# ProPrj___2025-12-14-16-26-23.net
KiCad netlist of a schematic drawn in EasyEDA Pro
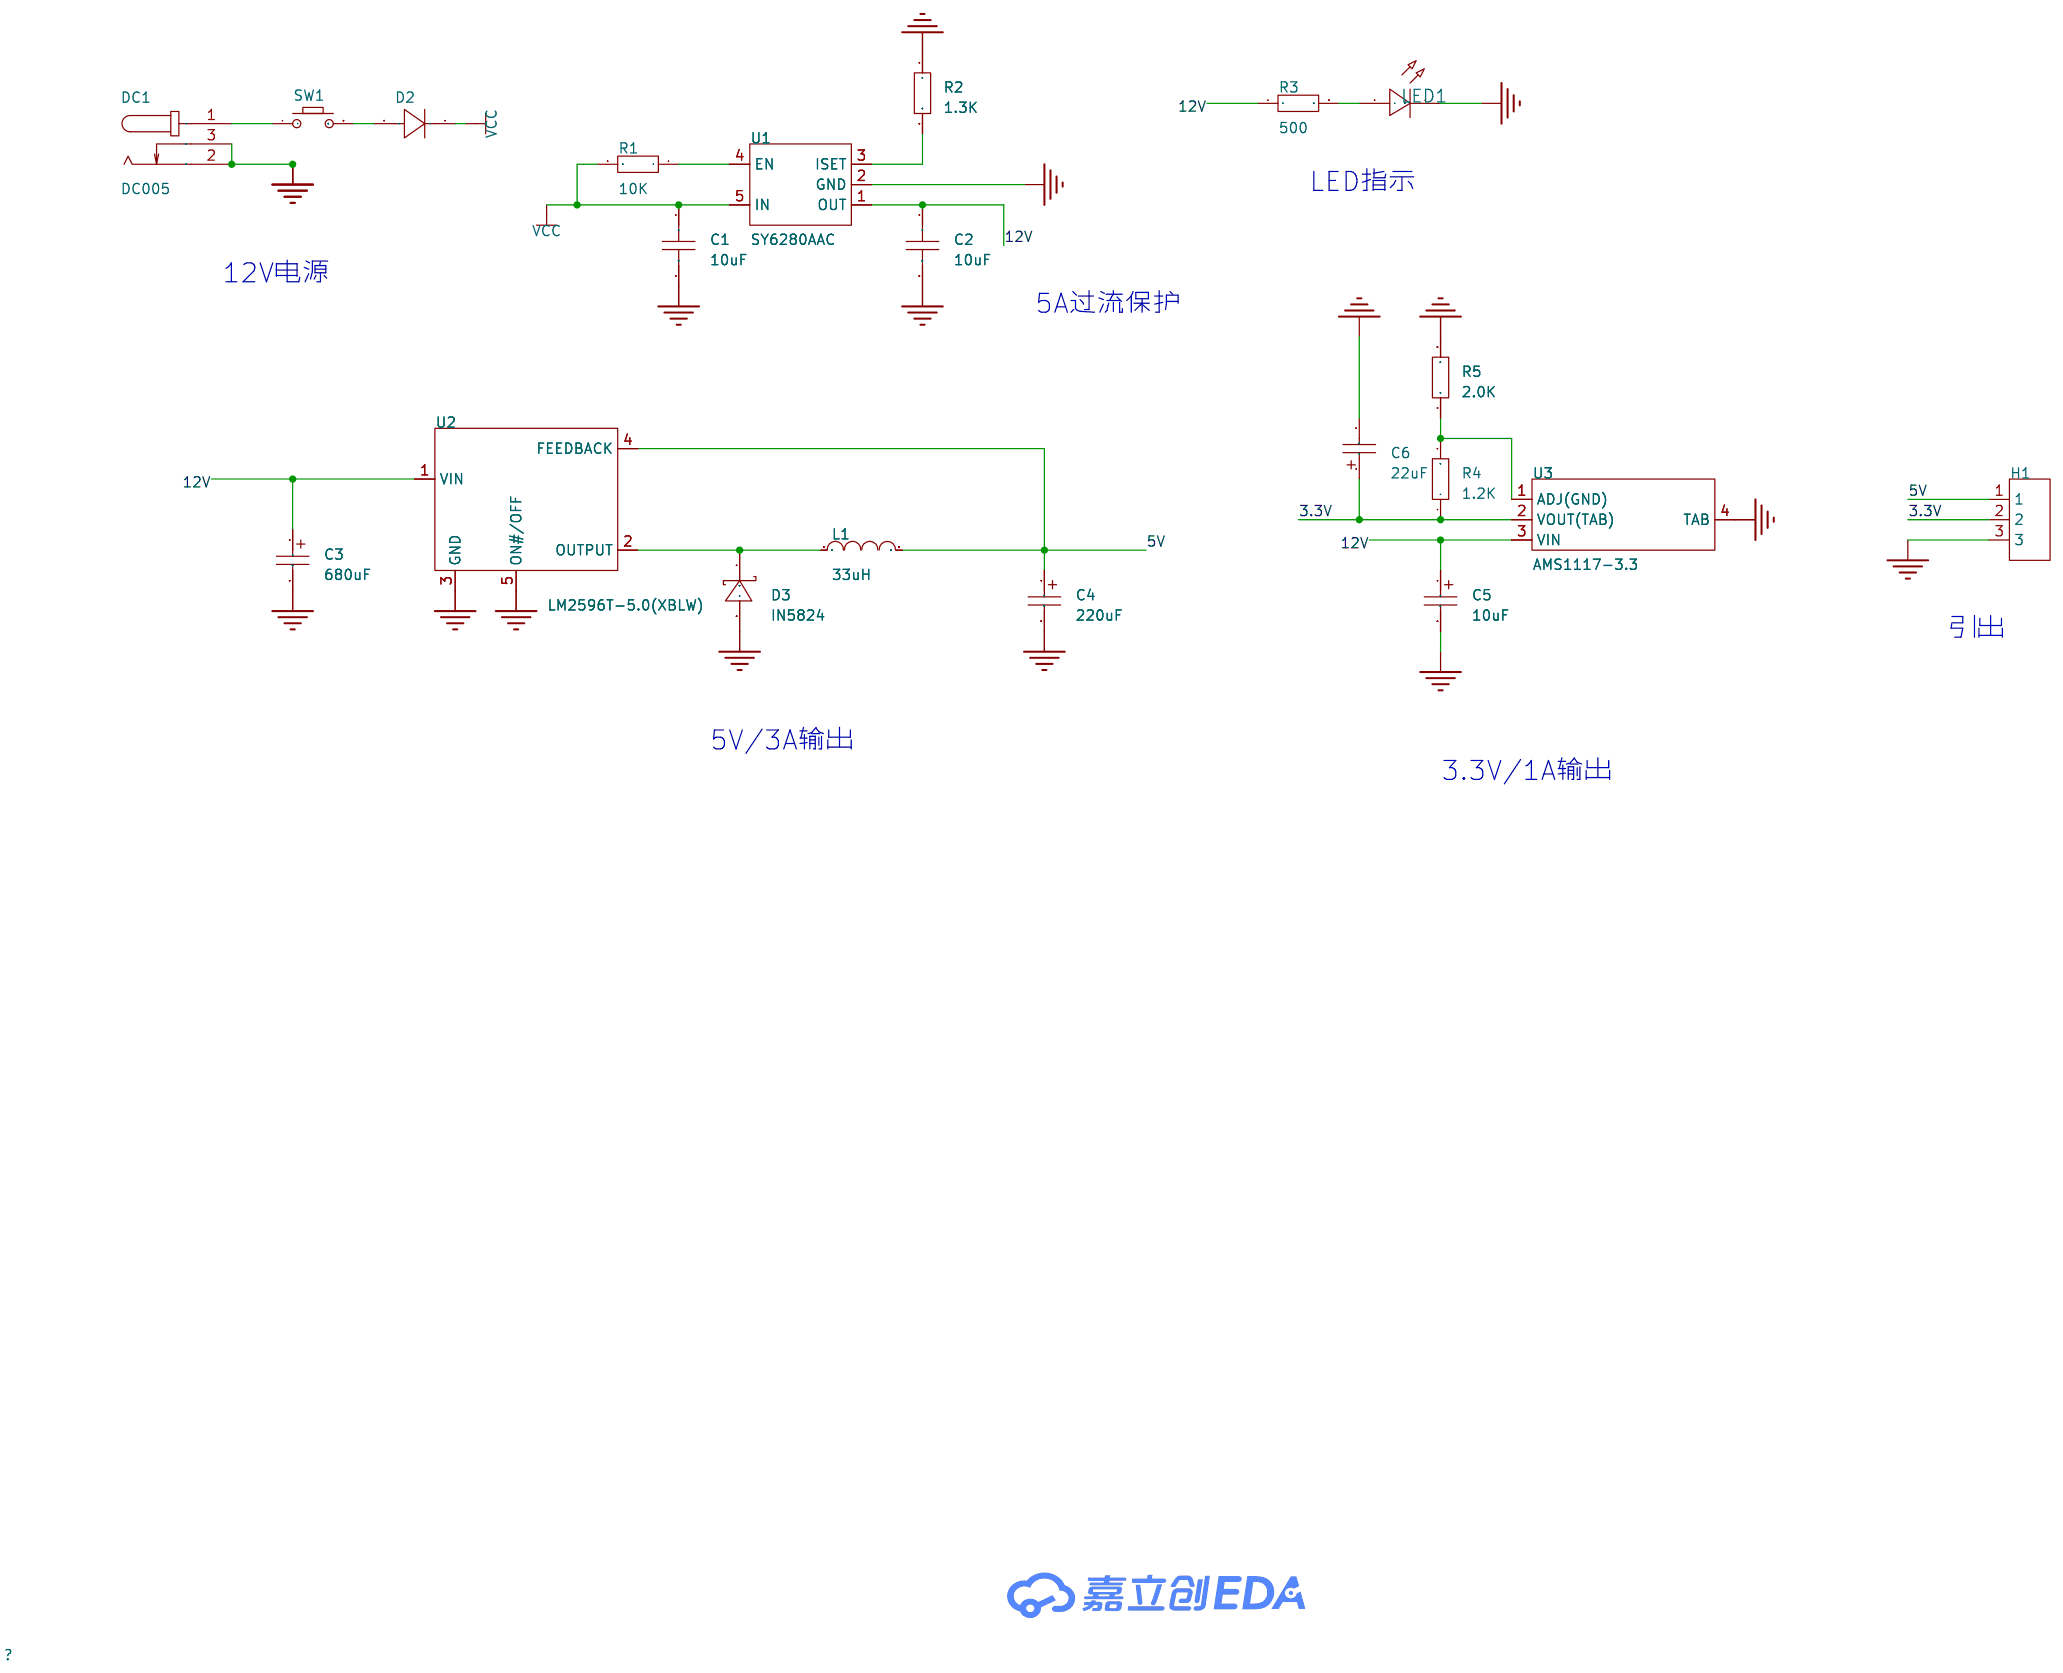
[diagram p0: schematic sheet]

(export (version "E")
  (design (tool "Eeschema 10.0.6"))
  (components
    (comp (ref "C1")
      (value "10uF")
      (footprint "easyedapro:C0603")
      (libsource (lib "easyedapro") (part "Capacitance"))
    )
    (comp (ref "C2")
      (value "10uF")
      (footprint "easyedapro:C0603")
      (libsource (lib "easyedapro") (part "Capacitance"))
    )
    (comp (ref "C3")
      (value "680uF")
      (footprint "easyedapro:C_Ele_SMD_3x5.4mm")
      (libsource (lib "easyedapro") (part "CAP"))
    )
    (comp (ref "C4")
      (value "220uF")
      (footprint "easyedapro:C_Ele_SMD_3x5.4mm")
      (libsource (lib "easyedapro") (part "CAP"))
    )
    (comp (ref "C5")
      (value "10uF")
      (footprint "easyedapro:C_Ele_SMD_3x5.4mm")
      (libsource (lib "easyedapro") (part "CAP"))
    )
    (comp (ref "C6")
      (value "22uF")
      (footprint "easyedapro:C_Ele_SMD_3x5.4mm")
      (libsource (lib "easyedapro") (part "CAP"))
    )
    (comp (ref "D2")
      (value "~")
      (footprint "easyedapro:DO_1N4007")
      (libsource (lib "easyedapro") (part "D_1N4007"))
    )
    (comp (ref "D3")
      (value "IN5824")
      (footprint "easyedapro:SMAF_L3.5-W2.6-LS4.7-RD")
      (libsource (lib "easyedapro") (part "IN5824"))
    )
    (comp (ref "DC1")
      (value "DC005")
      (footprint "easyedapro:DC-IN-TH_DC005")
      (description "连接器类型:DC电源插座;安装方式:弯插;触点内径:2mm;触点外径:6.3mm;额定电流:500mA;额定电压:12V;工作温度:-30°C~+70°C;")
      (fields (field (name "Manufacturer") "SHOU HAN(首韩)"))
      (libsource (lib "easyedapro") (part "DC005_C431533"))
    )
    (comp (ref "H1")
      (value "~")
      (footprint "easyedapro:HDR-TH_3P-P2.54-V-F")
      (libsource (lib "easyedapro") (part "PM254V-11-03-H85"))
    )
    (comp (ref "L1")
      (value "33uH")
      (footprint "easyedapro:L0603")
      (libsource (lib "easyedapro") (part "SDFL1608S100KTF"))
    )
    (comp (ref "LED1")
      (value "~")
      (footprint "easyedapro:LED_0603")
      (libsource (lib "easyedapro") (part "LED_R"))
    )
    (comp (ref "R1") (value "10K") (footprint "easyedapro:R0603") (libsource (lib "easyedapro") (part "电阻")))
    (comp (ref "R2") (value "1.3K") (footprint "easyedapro:R0603") (libsource (lib "easyedapro") (part "电阻")))
    (comp (ref "R3") (value "500") (footprint "easyedapro:R0603") (libsource (lib "easyedapro") (part "电阻")))
    (comp (ref "R4") (value "1.2K") (footprint "easyedapro:R0603") (libsource (lib "easyedapro") (part "电阻")))
    (comp (ref "R5") (value "2.0K") (footprint "easyedapro:R0603") (libsource (lib "easyedapro") (part "电阻")))
    (comp (ref "SW1")
      (value "~")
      (footprint "easyedapro:Key_TH_3.5x6x4.3")
      (libsource (lib "easyedapro") (part "Key_TH_3.5x6x4.3"))
    )
    (comp (ref "U1")
      (value "SY6280AAC")
      (footprint "easyedapro:SOT-23-5_L3.0-W1.7-P0.95-LS2.8-BR")
      (libsource (lib "easyedapro") (part "SY6280AAC_C9900003867"))
    )
    (comp (ref "U2")
      (value "LM2596T-5.0(XBLW)")
      (footprint "easyedapro:TO-220-5L_L10.2-W4.5-P1.71-L")
      (description "功能类型:降压型;工作电压:6V~40V;输出电压:5V;输出电流:3A;输出类型:固定;")
      (fields (field (name "Manufacturer") "XBLW(芯伯乐)"))
      (libsource (lib "easyedapro") (part "LM2596T-5.0(XBLW)"))
    )
    (comp (ref "U3")
      (value "AMS1117-3.3")
      (footprint "easyedapro:SOT-223-4_L6.5-W3.5-P2.30-LS7.0-BR")
      (description "输出类型:固定;工作电压:12V;输出电压:3.3V;输出电流:1A;电源纹波抑制比(PSRR):60dB@(120Hz);输出极性:正极;")
      (fields (field (name "Manufacturer") "UMW(友台半导体)"))
      (libsource (lib "easyedapro") (part "AMS1117-3.3_C347222"))
    )
  )
  (nets
    (net (code "1") (name "/3.3V") (class "Default")
      (node (ref "C6") (pin "1") (pinfunction "1_1") (pintype "input"))
      (node (ref "H1") (pin "2") (pinfunction "2_2") (pintype "unspecified"))
      (node (ref "R4") (pin "1") (pinfunction "1_1") (pintype "input"))
      (node (ref "U3") (pin "2") (pinfunction "VOUT(TAB)_2") (pintype "unspecified"))
    )
    (net (code "2") (name "/5V") (class "Default")
      (node (ref "C4") (pin "1") (pinfunction "1_1") (pintype "input"))
      (node (ref "H1") (pin "1") (pinfunction "1_1") (pintype "unspecified"))
      (node (ref "L1") (pin "2") (pinfunction "2_2") (pintype "unspecified"))
      (node (ref "U2") (pin "4") (pinfunction "FEEDBACK_4") (pintype "unspecified"))
    )
    (net (code "3") (name "/12V") (class "Default")
      (node (ref "C2") (pin "1") (pinfunction "1_1") (pintype "input"))
      (node (ref "C3") (pin "1") (pinfunction "1_1") (pintype "input"))
      (node (ref "C5") (pin "1") (pinfunction "1_1") (pintype "input"))
      (node (ref "R3") (pin "1") (pinfunction "1_1") (pintype "input"))
      (node (ref "U1") (pin "1") (pinfunction "OUT_1") (pintype "unspecified"))
      (node (ref "U2") (pin "1") (pinfunction "VIN_1") (pintype "unspecified"))
      (node (ref "U3") (pin "3") (pinfunction "VIN_3") (pintype "unspecified"))
    )
    (net (code "4") (name "GND") (class "Default")
      (node (ref "C1") (pin "2") (pinfunction "2_2") (pintype "input"))
      (node (ref "C2") (pin "2") (pinfunction "2_2") (pintype "input"))
      (node (ref "C3") (pin "2") (pinfunction "2_2") (pintype "input"))
      (node (ref "C4") (pin "2") (pinfunction "2_2") (pintype "input"))
      (node (ref "C5") (pin "2") (pinfunction "2_2") (pintype "input"))
      (node (ref "C6") (pin "2") (pinfunction "2_2") (pintype "input"))
      (node (ref "D3") (pin "2") (pinfunction "A_2") (pintype "unspecified"))
      (node (ref "DC1") (pin "2") (pinfunction "2_2") (pintype "unspecified"))
      (node (ref "DC1") (pin "3") (pinfunction "3_3") (pintype "unspecified"))
      (node (ref "H1") (pin "3") (pinfunction "3_3") (pintype "unspecified"))
      (node (ref "LED1") (pin "1") (pinfunction "C_1") (pintype "input"))
      (node (ref "R2") (pin "1") (pinfunction "1_1") (pintype "input"))
      (node (ref "R5") (pin "2") (pinfunction "2_2") (pintype "input"))
      (node (ref "U1") (pin "2") (pinfunction "GND_2") (pintype "unspecified"))
      (node (ref "U2") (pin "3") (pinfunction "GND_3") (pintype "unspecified"))
      (node (ref "U2") (pin "5") (pinfunction "ON#/OFF_5") (pintype "unspecified"))
      (node (ref "U3") (pin "4") (pinfunction "TAB_4") (pintype "unspecified"))
    )
    (net (code "5") (name "Net-(D2-A)") (class "Default")
      (node (ref "D2") (pin "2") (pinfunction "A_2") (pintype "input"))
      (node (ref "SW1") (pin "B") (pinfunction "B_B") (pintype "input"))
    )
    (net (code "6") (name "Net-(D3-C)") (class "Default")
      (node (ref "D3") (pin "1") (pinfunction "C_1") (pintype "unspecified"))
      (node (ref "L1") (pin "1") (pinfunction "1_1") (pintype "unspecified"))
      (node (ref "U2") (pin "2") (pinfunction "OUTPUT_2") (pintype "unspecified"))
    )
    (net (code "7") (name "Net-(DC1-Pad1)") (class "Default")
      (node (ref "DC1") (pin "1") (pinfunction "1_1") (pintype "unspecified"))
      (node (ref "SW1") (pin "A") (pinfunction "A_A") (pintype "input"))
    )
    (net (code "8") (name "Net-(LED1-A)") (class "Default")
      (node (ref "LED1") (pin "2") (pinfunction "A_2") (pintype "input"))
      (node (ref "R3") (pin "2") (pinfunction "2_2") (pintype "input"))
    )
    (net (code "9") (name "Net-(U1-EN)") (class "Default")
      (node (ref "R1") (pin "1") (pinfunction "1_1") (pintype "input"))
      (node (ref "U1") (pin "4") (pinfunction "EN_4") (pintype "unspecified"))
    )
    (net (code "10") (name "Net-(U1-ISET)") (class "Default")
      (node (ref "R2") (pin "2") (pinfunction "2_2") (pintype "input"))
      (node (ref "U1") (pin "3") (pinfunction "ISET_3") (pintype "unspecified"))
    )
    (net (code "11") (name "Net-(U3-ADJ(GND))") (class "Default")
      (node (ref "R4") (pin "2") (pinfunction "2_2") (pintype "input"))
      (node (ref "R5") (pin "1") (pinfunction "1_1") (pintype "input"))
      (node (ref "U3") (pin "1") (pinfunction "ADJ(GND)_1") (pintype "unspecified"))
    )
    (net (code "12") (name "VCC") (class "Default")
      (node (ref "C1") (pin "1") (pinfunction "1_1") (pintype "input"))
      (node (ref "D2") (pin "1") (pinfunction "K_1") (pintype "input"))
      (node (ref "R1") (pin "2") (pinfunction "2_2") (pintype "input"))
      (node (ref "U1") (pin "5") (pinfunction "IN_5") (pintype "unspecified"))
    )
  )
)
